# AntilogMM.net
KiCad netlist of a schematic drawn in EAGLE
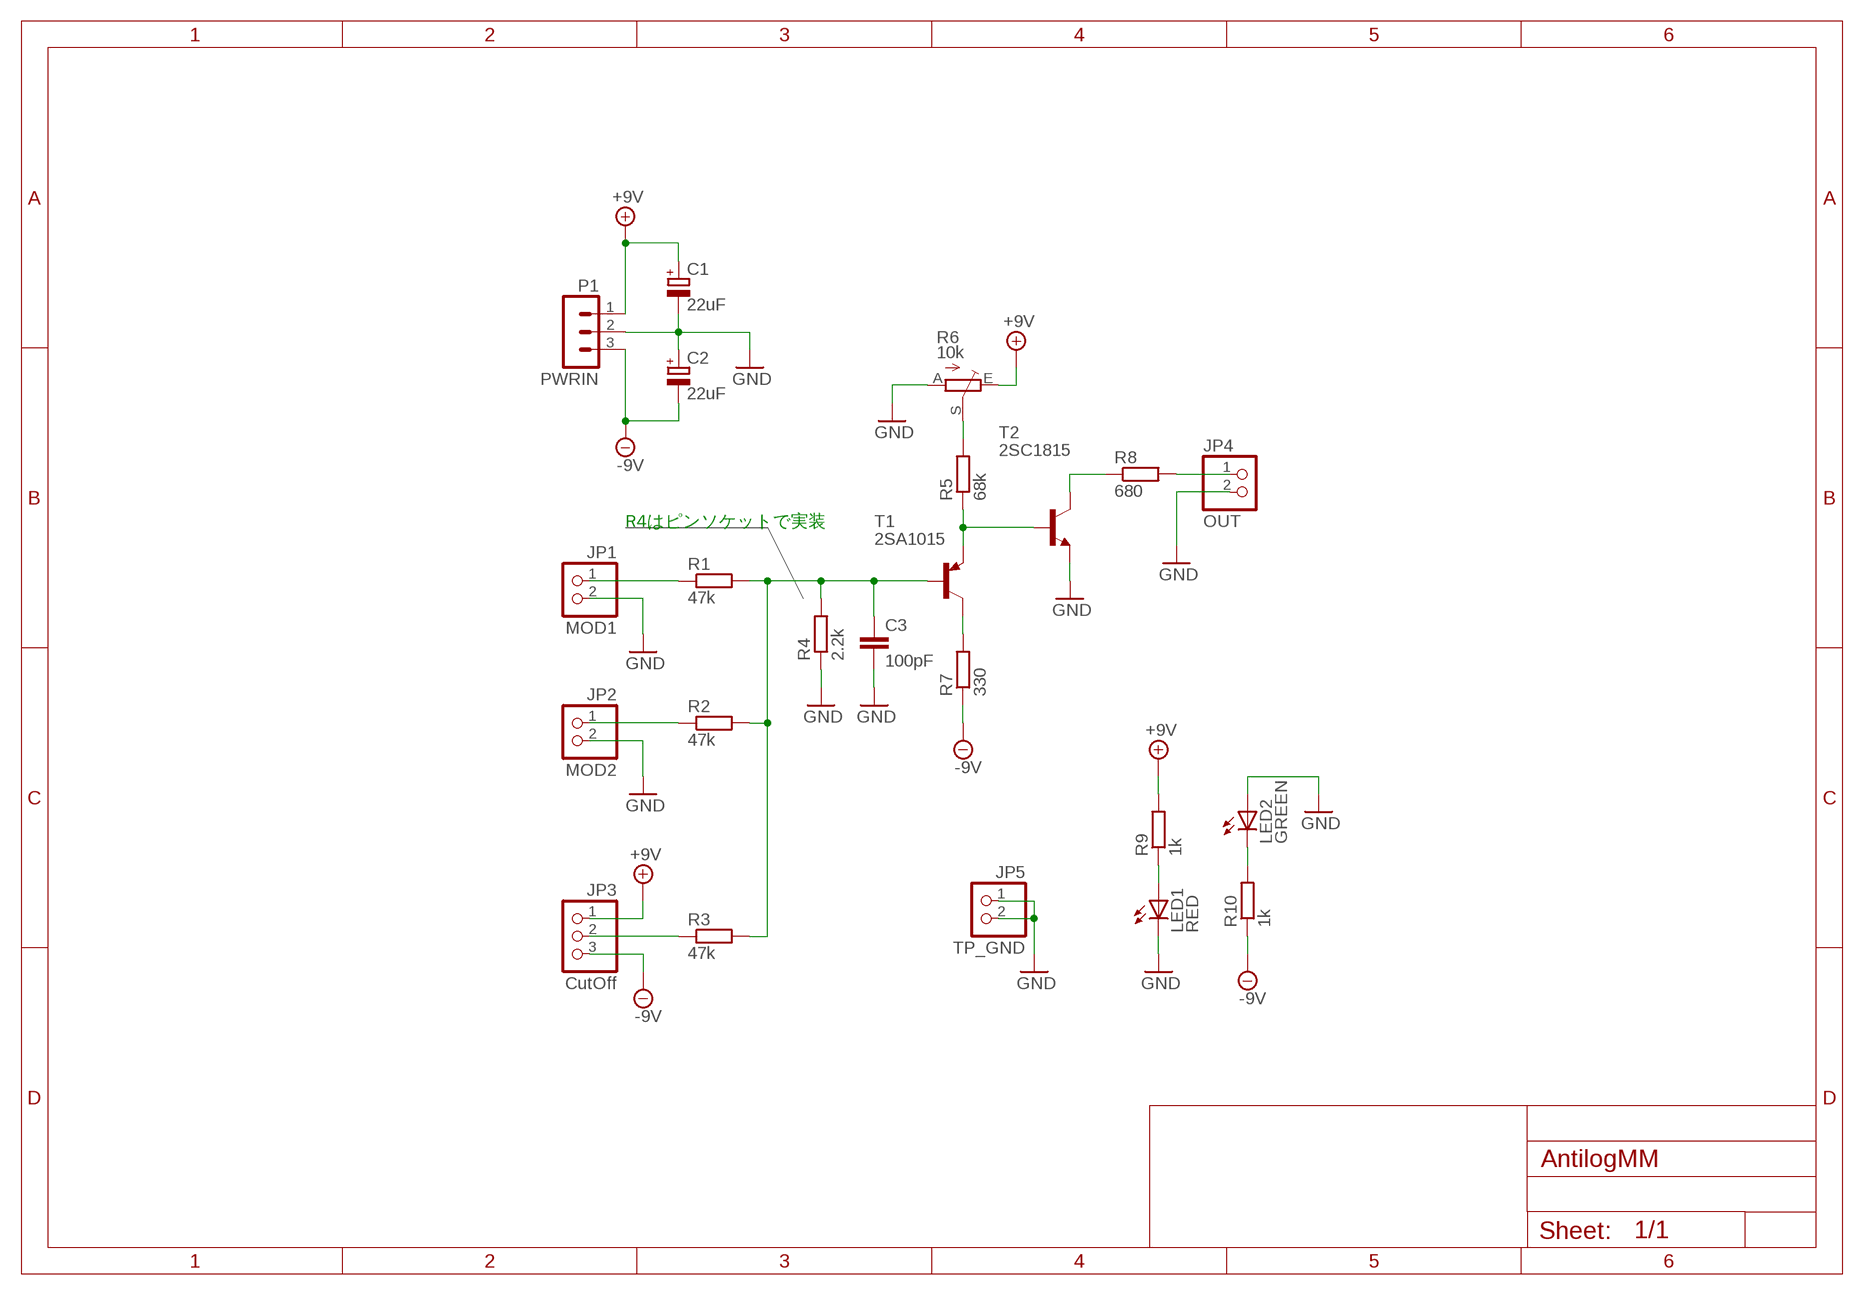
[diagram p0: schematic, sheet 1]

(export (version "E")
  (design (tool "Eeschema 10.0.6"))
  (components
    (comp (ref "C1")
      (value "22uF")
      (footprint "eagle-import:E2,5-6")
      (libsource (lib "eagle-import") (part "CPOL-EUE2.5-6"))
    )
    (comp (ref "C2")
      (value "22uF")
      (footprint "eagle-import:E2,5-6")
      (libsource (lib "eagle-import") (part "CPOL-EUE2.5-6"))
    )
    (comp (ref "C3")
      (value "100pF")
      (footprint "eagle-import:C050-024X044")
      (libsource (lib "eagle-import") (part "C-EU050-024X044"))
    )
    (comp (ref "JP1")
      (value "MOD1")
      (footprint "eagle-import:1X02")
      (libsource (lib "eagle-import") (part "PINHD-1X2"))
    )
    (comp (ref "JP2")
      (value "MOD2")
      (footprint "eagle-import:1X02")
      (libsource (lib "eagle-import") (part "PINHD-1X2"))
    )
    (comp (ref "JP3")
      (value "CutOff")
      (footprint "eagle-import:1X03")
      (libsource (lib "eagle-import") (part "PINHD-1X3"))
    )
    (comp (ref "JP4")
      (value "OUT")
      (footprint "eagle-import:1X02")
      (libsource (lib "eagle-import") (part "PINHD-1X2"))
    )
    (comp (ref "JP5")
      (value "TP_GND")
      (footprint "eagle-import:1X02")
      (libsource (lib "eagle-import") (part "PINHD-1X2"))
    )
    (comp (ref "LED1")
      (value "RED")
      (footprint "eagle-import:LED3MM")
      (libsource (lib "eagle-import") (part "LED3MM"))
    )
    (comp (ref "LED2")
      (value "GREEN")
      (footprint "eagle-import:LED3MM")
      (libsource (lib "eagle-import") (part "LED3MM"))
    )
    (comp (ref "P1")
      (value "PWRIN")
      (footprint "eagle-import:B3B-EH-A")
      (libsource (lib "eagle-import") (part "B3B-EH-A"))
    )
    (comp (ref "R1")
      (value "47k")
      (footprint "eagle-import:0207_7")
      (libsource (lib "eagle-import") (part "R-EU_0207/7"))
    )
    (comp (ref "R2")
      (value "47k")
      (footprint "eagle-import:0207_7")
      (libsource (lib "eagle-import") (part "R-EU_0207/7"))
    )
    (comp (ref "R3")
      (value "47k")
      (footprint "eagle-import:0207_7")
      (libsource (lib "eagle-import") (part "R-EU_0207/7"))
    )
    (comp (ref "R4")
      (value "2.2k")
      (footprint "eagle-import:0207_7")
      (libsource (lib "eagle-import") (part "R-EU_0207/7"))
    )
    (comp (ref "R5")
      (value "68k")
      (footprint "eagle-import:0207_7")
      (libsource (lib "eagle-import") (part "R-EU_0207/7"))
    )
    (comp (ref "R6")
      (value "10k")
      (footprint "eagle-import:B25P")
      (libsource (lib "eagle-import") (part "TRIM_EU-B25P"))
    )
    (comp (ref "R7")
      (value "330")
      (footprint "eagle-import:0207_7")
      (libsource (lib "eagle-import") (part "R-EU_0207/7"))
    )
    (comp (ref "R8")
      (value "680")
      (footprint "eagle-import:0207_7")
      (libsource (lib "eagle-import") (part "R-EU_0207/7"))
    )
    (comp (ref "R9")
      (value "1k")
      (footprint "eagle-import:0207_7")
      (libsource (lib "eagle-import") (part "R-EU_0207/7"))
    )
    (comp (ref "R10")
      (value "1k")
      (footprint "eagle-import:0207_7")
      (libsource (lib "eagle-import") (part "R-EU_0207/7"))
    )
    (comp (ref "T1")
      (value "2SA1015")
      (footprint "eagle-import:TO92-ECB")
      (libsource (lib "eagle-import") (part "-PNP-TO92-ECB"))
    )
    (comp (ref "T2")
      (value "2SC1815")
      (footprint "eagle-import:TO92-ECB")
      (libsource (lib "eagle-import") (part "-NPN-TO92-ECB"))
    )
  )
  (nets
    (net (code "1") (name "+9V") (class "Default")
      (node (ref "C1") (pin "+") (pinfunction "+_+") (pintype "passive"))
      (node (ref "JP3") (pin "1") (pinfunction "1_1") (pintype "passive"))
      (node (ref "P1") (pin "1") (pinfunction "1_1") (pintype "passive"))
      (node (ref "R6") (pin "E") (pinfunction "E_E") (pintype "passive"))
      (node (ref "R9") (pin "2") (pinfunction "2_2") (pintype "passive"))
    )
    (net (code "2") (name "-9V") (class "Default")
      (node (ref "C2") (pin "-") (pinfunction "-_-") (pintype "passive"))
      (node (ref "JP3") (pin "3") (pinfunction "3_3") (pintype "passive"))
      (node (ref "P1") (pin "3") (pinfunction "3_3") (pintype "passive"))
      (node (ref "R10") (pin "1") (pinfunction "1_1") (pintype "passive"))
      (node (ref "R7") (pin "1") (pinfunction "1_1") (pintype "passive"))
    )
    (net (code "3") (name "GND") (class "Default")
      (node (ref "C1") (pin "-") (pinfunction "-_-") (pintype "passive"))
      (node (ref "C2") (pin "+") (pinfunction "+_+") (pintype "passive"))
      (node (ref "C3") (pin "2") (pinfunction "2_2") (pintype "passive"))
      (node (ref "JP1") (pin "2") (pinfunction "2_2") (pintype "passive"))
      (node (ref "JP2") (pin "2") (pinfunction "2_2") (pintype "passive"))
      (node (ref "JP4") (pin "2") (pinfunction "2_2") (pintype "passive"))
      (node (ref "JP5") (pin "1") (pinfunction "1_1") (pintype "passive"))
      (node (ref "JP5") (pin "2") (pinfunction "2_2") (pintype "passive"))
      (node (ref "LED1") (pin "K") (pinfunction "C_K") (pintype "passive"))
      (node (ref "LED2") (pin "A") (pinfunction "A_A") (pintype "passive"))
      (node (ref "P1") (pin "2") (pinfunction "2_2") (pintype "passive"))
      (node (ref "R4") (pin "1") (pinfunction "1_1") (pintype "passive"))
      (node (ref "R6") (pin "A") (pinfunction "A_A") (pintype "passive"))
      (node (ref "T2") (pin "E") (pinfunction "E_E") (pintype "passive"))
    )
    (net (code "4") (name "Net-(C3-Pad1)") (class "Default")
      (node (ref "C3") (pin "1") (pinfunction "1_1") (pintype "passive"))
      (node (ref "R1") (pin "2") (pinfunction "2_2") (pintype "passive"))
      (node (ref "R2") (pin "2") (pinfunction "2_2") (pintype "passive"))
      (node (ref "R3") (pin "2") (pinfunction "2_2") (pintype "passive"))
      (node (ref "R4") (pin "2") (pinfunction "2_2") (pintype "passive"))
      (node (ref "T1") (pin "B") (pinfunction "B_B") (pintype "passive"))
    )
    (net (code "5") (name "Net-(JP1-Pad1)") (class "Default")
      (node (ref "JP1") (pin "1") (pinfunction "1_1") (pintype "passive"))
      (node (ref "R1") (pin "1") (pinfunction "1_1") (pintype "passive"))
    )
    (net (code "6") (name "Net-(JP2-Pad1)") (class "Default")
      (node (ref "JP2") (pin "1") (pinfunction "1_1") (pintype "passive"))
      (node (ref "R2") (pin "1") (pinfunction "1_1") (pintype "passive"))
    )
    (net (code "7") (name "Net-(JP3-Pad2)") (class "Default")
      (node (ref "JP3") (pin "2") (pinfunction "2_2") (pintype "passive"))
      (node (ref "R3") (pin "1") (pinfunction "1_1") (pintype "passive"))
    )
    (net (code "8") (name "Net-(JP4-Pad1)") (class "Default")
      (node (ref "JP4") (pin "1") (pinfunction "1_1") (pintype "passive"))
      (node (ref "R8") (pin "2") (pinfunction "2_2") (pintype "passive"))
    )
    (net (code "9") (name "Net-(LED1-PadA)") (class "Default")
      (node (ref "LED1") (pin "A") (pinfunction "A_A") (pintype "passive"))
      (node (ref "R9") (pin "1") (pinfunction "1_1") (pintype "passive"))
    )
    (net (code "10") (name "Net-(LED2-C)") (class "Default")
      (node (ref "LED2") (pin "K") (pinfunction "C_K") (pintype "passive"))
      (node (ref "R10") (pin "2") (pinfunction "2_2") (pintype "passive"))
    )
    (net (code "11") (name "Net-(R5-Pad1)") (class "Default")
      (node (ref "R5") (pin "1") (pinfunction "1_1") (pintype "passive"))
      (node (ref "T1") (pin "E") (pinfunction "E_E") (pintype "passive"))
      (node (ref "T2") (pin "B") (pinfunction "B_B") (pintype "passive"))
    )
    (net (code "12") (name "Net-(R5-Pad2)") (class "Default")
      (node (ref "R5") (pin "2") (pinfunction "2_2") (pintype "passive"))
      (node (ref "R6") (pin "S") (pinfunction "S_S") (pintype "passive"))
    )
    (net (code "13") (name "Net-(R7-Pad2)") (class "Default")
      (node (ref "R7") (pin "2") (pinfunction "2_2") (pintype "passive"))
      (node (ref "T1") (pin "C") (pinfunction "C_C") (pintype "passive"))
    )
    (net (code "14") (name "Net-(R8-Pad1)") (class "Default")
      (node (ref "R8") (pin "1") (pinfunction "1_1") (pintype "passive"))
      (node (ref "T2") (pin "C") (pinfunction "C_C") (pintype "passive"))
    )
  )
)
